# CSS811_BME280_Breakout.net
KiCad netlist of a schematic drawn in EAGLE
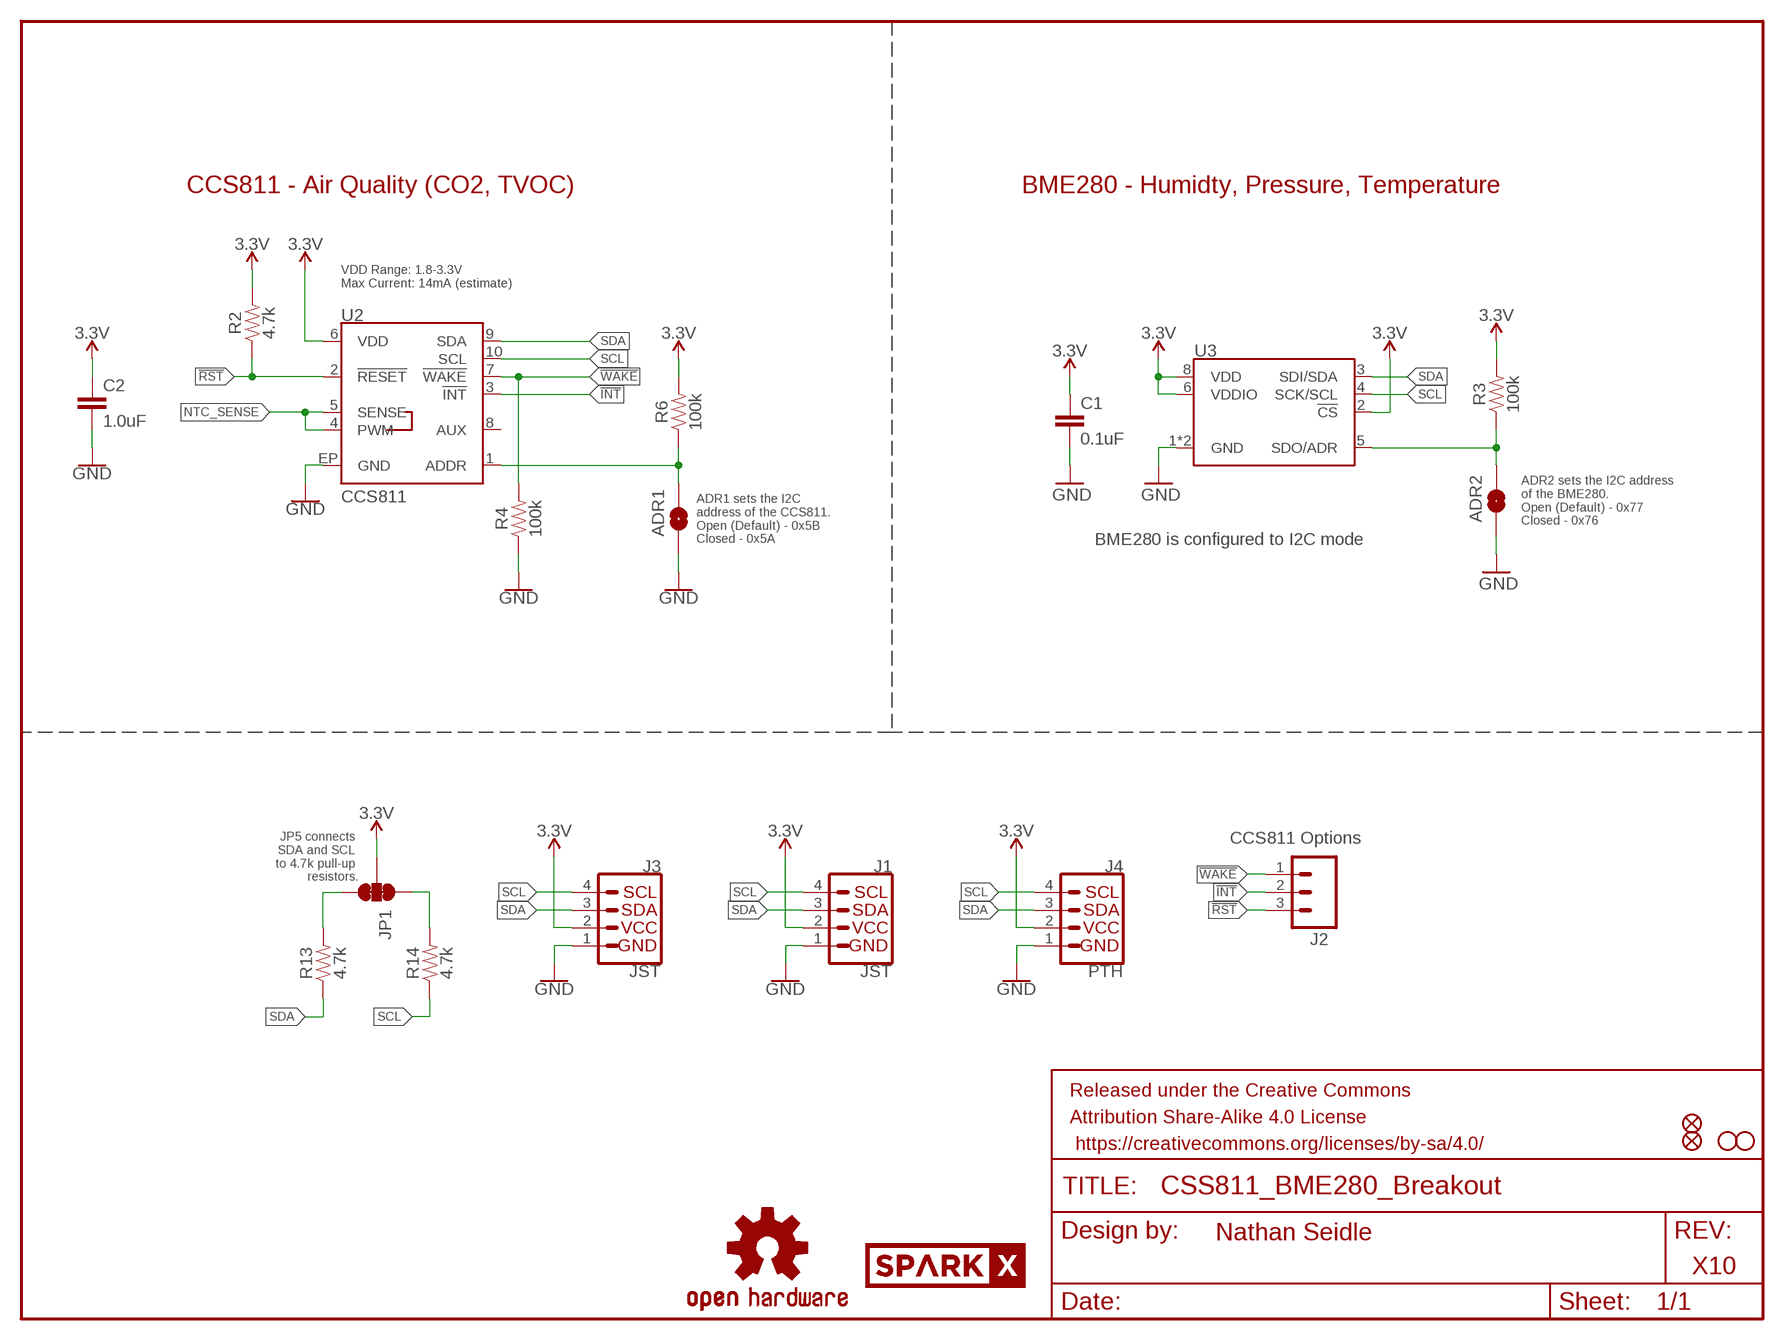
[diagram p0: schematic, sheet 1]

(export (version "E")
  (design (tool "Eeschema 10.0.6"))
  (components
    (comp (ref "ADR1")
      (value "JUMPER-SMT_2_NO_SILK")
      (footprint "eagle-import:SMT-JUMPER_2_NO_SILK")
      (libsource (lib "eagle-import") (part "JUMPER-SMT_2_NO_SILK"))
    )
    (comp (ref "ADR2")
      (value "JUMPER-SMT_2_NO_SILK")
      (footprint "eagle-import:SMT-JUMPER_2_NO_SILK")
      (libsource (lib "eagle-import") (part "JUMPER-SMT_2_NO_SILK"))
    )
    (comp (ref "C1")
      (value "0.1uF")
      (footprint "eagle-import:0603-CAP")
      (libsource (lib "eagle-import") (part "0.1UF-25V-5%(0603)"))
    )
    (comp (ref "C2")
      (value "1.0uF")
      (footprint "eagle-import:0603")
      (libsource (lib "eagle-import") (part "1.0UF-0603-16V-10%"))
    )
    (comp (ref "FD1")
      (value "FIDUCIAL1X2")
      (footprint "eagle-import:FIDUCIAL-1X2")
      (libsource (lib "eagle-import") (part "FIDUCIAL1X2"))
    )
    (comp (ref "FD2")
      (value "FIDUCIAL1X2")
      (footprint "eagle-import:FIDUCIAL-1X2")
      (libsource (lib "eagle-import") (part "FIDUCIAL1X2"))
    )
    (comp (ref "FRAME1")
      (value "FRAME-LETTER")
      (footprint "eagle-import:CREATIVE_COMMONS")
      (libsource (lib "eagle-import") (part "FRAME-LETTER"))
    )
    (comp (ref "H2")
      (value "STAND-OFF")
      (footprint "eagle-import:STAND-OFF")
      (libsource (lib "eagle-import") (part "STAND-OFF"))
    )
    (comp (ref "H4")
      (value "STAND-OFF")
      (footprint "eagle-import:STAND-OFF")
      (libsource (lib "eagle-import") (part "STAND-OFF"))
    )
    (comp (ref "J1")
      (value "JST")
      (footprint "eagle-import:1X04_1MM_RA")
      (libsource (lib "eagle-import") (part "I2C_STANDARDJS-1MM"))
    )
    (comp (ref "J2")
      (value "CCS811 Options")
      (footprint "eagle-import:1X03_NO_SILK")
      (libsource (lib "eagle-import") (part "CONN_031X03_NO_SILK"))
    )
    (comp (ref "J3")
      (value "JST")
      (footprint "eagle-import:1X04_1MM_RA")
      (libsource (lib "eagle-import") (part "I2C_STANDARDJS-1MM"))
    )
    (comp (ref "J4")
      (value "PTH")
      (footprint "eagle-import:1X04_NO_SILK")
      (libsource (lib "eagle-import") (part "I2C_STANDARD_NO_SILK"))
    )
    (comp (ref "JP1")
      (value "JUMPER-SMT_3_2-NC_TRACE_SILK")
      (footprint "eagle-import:SMT-JUMPER_3_2-NC_TRACE_SILK")
      (libsource (lib "eagle-import") (part "JUMPER-SMT_3_2-NC_TRACE_SILK"))
    )
    (comp (ref "LOGO4")
      (value "OSHW-LOGOS")
      (footprint "eagle-import:OSHW-LOGO-S")
      (libsource (lib "eagle-import") (part "OSHW-LOGOS"))
    )
    (comp (ref "R2")
      (value "4.7k")
      (footprint "eagle-import:0603")
      (libsource (lib "eagle-import") (part "4.7KOHM-0603-1/10W-1%"))
    )
    (comp (ref "R3")
      (value "100k")
      (footprint "eagle-import:0603")
      (libsource (lib "eagle-import") (part "100KOHM-0603-1/10W-1%"))
    )
    (comp (ref "R4")
      (value "100k")
      (footprint "eagle-import:0603")
      (libsource (lib "eagle-import") (part "100KOHM-0603-1/10W-1%"))
    )
    (comp (ref "R6")
      (value "100k")
      (footprint "eagle-import:0603")
      (libsource (lib "eagle-import") (part "100KOHM-0603-1/10W-1%"))
    )
    (comp (ref "R13")
      (value "4.7k")
      (footprint "eagle-import:0603")
      (libsource (lib "eagle-import") (part "4.7KOHM-0603-1/10W-1%"))
    )
    (comp (ref "R14")
      (value "4.7k")
      (footprint "eagle-import:0603")
      (libsource (lib "eagle-import") (part "4.7KOHM-0603-1/10W-1%"))
    )
    (comp (ref "U$1")
      (value "SPARKX-LOGO4")
      (footprint "eagle-import:SPARKX-MEDIUM")
      (libsource (lib "eagle-import") (part "SPARKX-LOGO4"))
    )
    (comp (ref "U$2")
      (value "SPARKX-LOGO4")
      (footprint "eagle-import:SPARKX-MEDIUM")
      (libsource (lib "eagle-import") (part "SPARKX-LOGO4"))
    )
    (comp (ref "U2")
      (value "CCS811")
      (footprint "eagle-import:LGA10")
      (libsource (lib "eagle-import") (part "CCS811PRODUCTION"))
    )
    (comp (ref "U3")
      (value "BME280")
      (footprint "eagle-import:BME280_LGA")
      (libsource (lib "eagle-import") (part "BME280"))
    )
  )
  (nets
    (net (code "1") (name "/~{INT}") (class "Default")
      (node (ref "J2") (pin "2") (pinfunction "2_2") (pintype "passive"))
      (node (ref "U2") (pin "3") (pinfunction "~{INT}_3") (pintype "bidirectional"))
    )
    (net (code "2") (name "/~{RST}") (class "Default")
      (node (ref "J2") (pin "3") (pinfunction "3_3") (pintype "passive"))
      (node (ref "R2") (pin "1") (pinfunction "1_1") (pintype "passive"))
      (node (ref "U2") (pin "2") (pinfunction "~{RESET}_2") (pintype "bidirectional"))
    )
    (net (code "3") (name "/~{WAKE}") (class "Default")
      (node (ref "J2") (pin "1") (pinfunction "1_1") (pintype "passive"))
      (node (ref "R4") (pin "2") (pinfunction "2_2") (pintype "passive"))
      (node (ref "U2") (pin "7") (pinfunction "~{WAKE}_7") (pintype "bidirectional"))
    )
    (net (code "4") (name "3.3V") (class "Default")
      (node (ref "C1") (pin "1") (pinfunction "1_1") (pintype "passive"))
      (node (ref "C2") (pin "1") (pinfunction "1_1") (pintype "passive"))
      (node (ref "J1") (pin "2") (pinfunction "VCC_2") (pintype "power_in"))
      (node (ref "J3") (pin "2") (pinfunction "VCC_2") (pintype "power_in"))
      (node (ref "J4") (pin "2") (pinfunction "VCC_2") (pintype "power_in"))
      (node (ref "JP1") (pin "2") (pinfunction "2_2") (pintype "passive"))
      (node (ref "R2") (pin "2") (pinfunction "2_2") (pintype "passive"))
      (node (ref "R3") (pin "2") (pinfunction "2_2") (pintype "passive"))
      (node (ref "R6") (pin "2") (pinfunction "2_2") (pintype "passive"))
      (node (ref "U2") (pin "6") (pinfunction "VDD_6") (pintype "bidirectional"))
      (node (ref "U3") (pin "2") (pinfunction "~{CS}_2") (pintype "bidirectional"))
      (node (ref "U3") (pin "6") (pinfunction "VDDIO_6") (pintype "bidirectional"))
      (node (ref "U3") (pin "8") (pinfunction "VDD_8") (pintype "bidirectional"))
    )
    (net (code "5") (name "GND") (class "Default")
      (node (ref "ADR1") (pin "1") (pinfunction "1_1") (pintype "passive"))
      (node (ref "ADR2") (pin "1") (pinfunction "1_1") (pintype "passive"))
      (node (ref "C1") (pin "2") (pinfunction "2_2") (pintype "passive"))
      (node (ref "C2") (pin "2") (pinfunction "2_2") (pintype "passive"))
      (node (ref "J1") (pin "1") (pinfunction "GND_1") (pintype "power_in"))
      (node (ref "J3") (pin "1") (pinfunction "GND_1") (pintype "power_in"))
      (node (ref "J4") (pin "1") (pinfunction "GND_1") (pintype "power_in"))
      (node (ref "R4") (pin "1") (pinfunction "1_1") (pintype "passive"))
      (node (ref "U2") (pin "EP") (pinfunction "GND_EP") (pintype "bidirectional"))
      (node (ref "U3") (pin "1") (pinfunction "GND_1") (pintype "bidirectional"))
      (node (ref "U3") (pin "7") (pinfunction "GND_7") (pintype "bidirectional"))
    )
    (net (code "6") (name "NTC_SENSE") (class "Default")
      (node (ref "U2") (pin "4") (pinfunction "PWM_4") (pintype "bidirectional"))
      (node (ref "U2") (pin "5") (pinfunction "SENSE_5") (pintype "bidirectional"))
    )
    (net (code "7") (name "Net-(JP1-Pad1)") (class "Default")
      (node (ref "JP1") (pin "1") (pinfunction "1_1") (pintype "passive"))
      (node (ref "R14") (pin "2") (pinfunction "2_2") (pintype "passive"))
    )
    (net (code "8") (name "Net-(JP1-Pad3)") (class "Default")
      (node (ref "JP1") (pin "3") (pinfunction "3_3") (pintype "passive"))
      (node (ref "R13") (pin "2") (pinfunction "2_2") (pintype "passive"))
    )
    (net (code "9") (name "Net-(U2-ADDR)") (class "Default")
      (node (ref "ADR1") (pin "2") (pinfunction "2_2") (pintype "passive"))
      (node (ref "R6") (pin "1") (pinfunction "1_1") (pintype "passive"))
      (node (ref "U2") (pin "1") (pinfunction "ADDR_1") (pintype "bidirectional"))
    )
    (net (code "10") (name "Net-(U3-SDO{slash}ADR)") (class "Default")
      (node (ref "ADR2") (pin "2") (pinfunction "2_2") (pintype "passive"))
      (node (ref "R3") (pin "1") (pinfunction "1_1") (pintype "passive"))
      (node (ref "U3") (pin "5") (pinfunction "SDO/ADR_5") (pintype "bidirectional"))
    )
    (net (code "11") (name "SCL") (class "Default")
      (node (ref "J1") (pin "4") (pinfunction "SCL_4") (pintype "passive"))
      (node (ref "J3") (pin "4") (pinfunction "SCL_4") (pintype "passive"))
      (node (ref "J4") (pin "4") (pinfunction "SCL_4") (pintype "passive"))
      (node (ref "R14") (pin "1") (pinfunction "1_1") (pintype "passive"))
      (node (ref "U2") (pin "10") (pinfunction "SCL_10") (pintype "bidirectional"))
      (node (ref "U3") (pin "4") (pinfunction "SCK/SCL_4") (pintype "bidirectional"))
    )
    (net (code "12") (name "SDA") (class "Default")
      (node (ref "J1") (pin "3") (pinfunction "SDA_3") (pintype "passive"))
      (node (ref "J3") (pin "3") (pinfunction "SDA_3") (pintype "passive"))
      (node (ref "J4") (pin "3") (pinfunction "SDA_3") (pintype "passive"))
      (node (ref "R13") (pin "1") (pinfunction "1_1") (pintype "passive"))
      (node (ref "U2") (pin "9") (pinfunction "SDA_9") (pintype "bidirectional"))
      (node (ref "U3") (pin "3") (pinfunction "SDI/SDA_3") (pintype "bidirectional"))
    )
    (net (code "13") (name "unconnected-(U2-AUX-Pad8)") (class "Default")
      (node (ref "U2") (pin "8") (pinfunction "AUX_8") (pintype "bidirectional"))
    )
  )
)
